# Minna_IO.net
KiCad netlist of a schematic drawn in Altium Designer
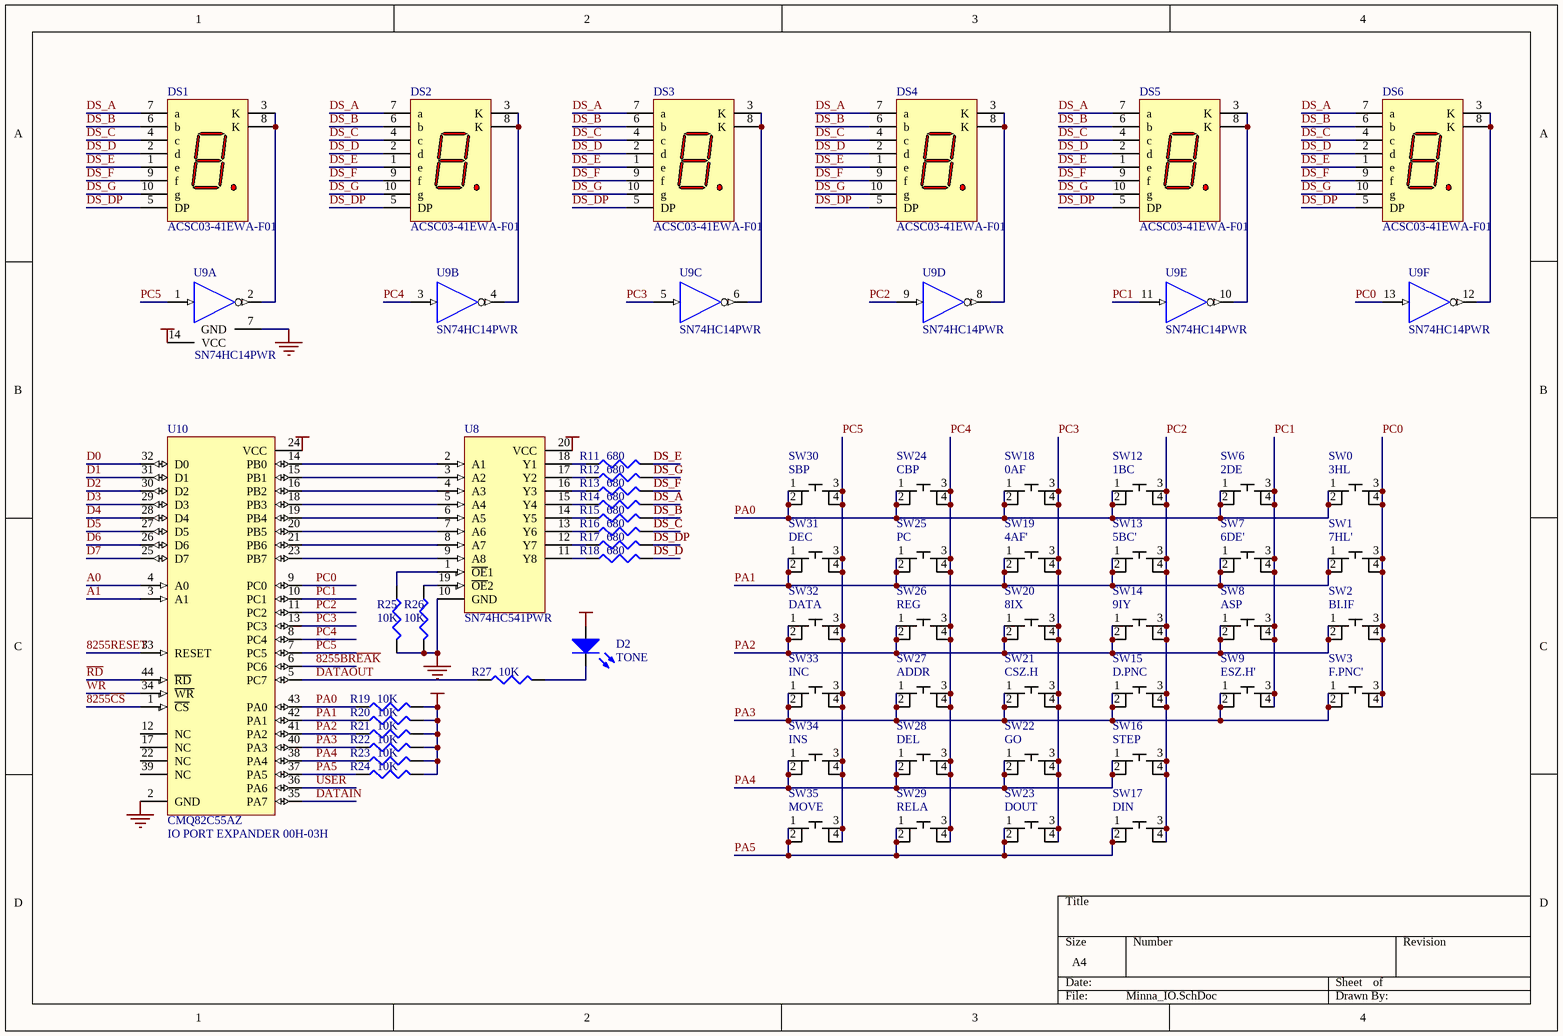
[diagram p0: Minna_IO.SchDoc]

(export (version "E")
  (design (tool "Eeschema 10.0.6"))
  (components
    (comp (ref "D2")
      (value "TONE")
      (footprint "Minna Project:APG1608")
      (description "LED 1.6X0.8MM 571NM GRN CLR SMD")
      (libsource (lib "Minna Project") (part "APG1608CGKC/T"))
    )
    (comp (ref "DS1")
      (value "ACSC03-41EWA-F01")
      (footprint "Minna Project:ACSC03-41EWA-F01")
      (description "DISPLAY 0.3\" 627NM SGL RED SMD")
      (libsource (lib "Minna Project") (part "ACSC03-41EWA-F01"))
    )
    (comp (ref "DS2")
      (value "ACSC03-41EWA-F01")
      (footprint "Minna Project:ACSC03-41EWA-F01")
      (description "DISPLAY 0.3\" 627NM SGL RED SMD")
      (libsource (lib "Minna Project") (part "ACSC03-41EWA-F01"))
    )
    (comp (ref "DS3")
      (value "ACSC03-41EWA-F01")
      (footprint "Minna Project:ACSC03-41EWA-F01")
      (description "DISPLAY 0.3\" 627NM SGL RED SMD")
      (libsource (lib "Minna Project") (part "ACSC03-41EWA-F01"))
    )
    (comp (ref "DS4")
      (value "ACSC03-41EWA-F01")
      (footprint "Minna Project:ACSC03-41EWA-F01")
      (description "DISPLAY 0.3\" 627NM SGL RED SMD")
      (libsource (lib "Minna Project") (part "ACSC03-41EWA-F01"))
    )
    (comp (ref "DS5")
      (value "ACSC03-41EWA-F01")
      (footprint "Minna Project:ACSC03-41EWA-F01")
      (description "DISPLAY 0.3\" 627NM SGL RED SMD")
      (libsource (lib "Minna Project") (part "ACSC03-41EWA-F01"))
    )
    (comp (ref "DS6")
      (value "ACSC03-41EWA-F01")
      (footprint "Minna Project:ACSC03-41EWA-F01")
      (description "DISPLAY 0.3\" 627NM SGL RED SMD")
      (libsource (lib "Minna Project") (part "ACSC03-41EWA-F01"))
    )
    (comp (ref "R11")
      (value "680")
      (footprint "Minna Project:0603")
      (description "RES 680 OHM 1/10W 1% 0603 SMD")
      (libsource (lib "Minna Project") (part "MCR03EZPFX"))
    )
    (comp (ref "R12")
      (value "680")
      (footprint "Minna Project:0603")
      (description "RES 680 OHM 1/10W 1% 0603 SMD")
      (libsource (lib "Minna Project") (part "MCR03EZPFX"))
    )
    (comp (ref "R13")
      (value "680")
      (footprint "Minna Project:0603")
      (description "RES 680 OHM 1/10W 1% 0603 SMD")
      (libsource (lib "Minna Project") (part "MCR03EZPFX"))
    )
    (comp (ref "R14")
      (value "680")
      (footprint "Minna Project:0603")
      (description "RES 680 OHM 1/10W 1% 0603 SMD")
      (libsource (lib "Minna Project") (part "MCR03EZPFX"))
    )
    (comp (ref "R15")
      (value "680")
      (footprint "Minna Project:0603")
      (description "RES 680 OHM 1/10W 1% 0603 SMD")
      (libsource (lib "Minna Project") (part "MCR03EZPFX"))
    )
    (comp (ref "R16")
      (value "680")
      (footprint "Minna Project:0603")
      (description "RES 680 OHM 1/10W 1% 0603 SMD")
      (libsource (lib "Minna Project") (part "MCR03EZPFX"))
    )
    (comp (ref "R17")
      (value "680")
      (footprint "Minna Project:0603")
      (description "RES 680 OHM 1/10W 1% 0603 SMD")
      (libsource (lib "Minna Project") (part "MCR03EZPFX"))
    )
    (comp (ref "R18")
      (value "680")
      (footprint "Minna Project:0603")
      (description "RES 680 OHM 1/10W 1% 0603 SMD")
      (libsource (lib "Minna Project") (part "MCR03EZPFX"))
    )
    (comp (ref "R19")
      (value "10K")
      (footprint "Minna Project:0603")
      (description "RES 10.0K OHM 1/10W 1% 0603 SMD")
      (libsource (lib "Minna Project") (part "MCR03EZPFX"))
    )
    (comp (ref "R20")
      (value "10K")
      (footprint "Minna Project:0603")
      (description "RES 10.0K OHM 1/10W 1% 0603 SMD")
      (libsource (lib "Minna Project") (part "MCR03EZPFX"))
    )
    (comp (ref "R21")
      (value "10K")
      (footprint "Minna Project:0603")
      (description "RES 10.0K OHM 1/10W 1% 0603 SMD")
      (libsource (lib "Minna Project") (part "MCR03EZPFX"))
    )
    (comp (ref "R22")
      (value "10K")
      (footprint "Minna Project:0603")
      (description "RES 10.0K OHM 1/10W 1% 0603 SMD")
      (libsource (lib "Minna Project") (part "MCR03EZPFX"))
    )
    (comp (ref "R23")
      (value "10K")
      (footprint "Minna Project:0603")
      (description "RES 10.0K OHM 1/10W 1% 0603 SMD")
      (libsource (lib "Minna Project") (part "MCR03EZPFX"))
    )
    (comp (ref "R24")
      (value "10K")
      (footprint "Minna Project:0603")
      (description "RES 10.0K OHM 1/10W 1% 0603 SMD")
      (libsource (lib "Minna Project") (part "MCR03EZPFX"))
    )
    (comp (ref "R25")
      (value "10K")
      (footprint "Minna Project:0603")
      (description "RES 10.0K OHM 1/10W 1% 0603 SMD")
      (libsource (lib "Minna Project") (part "MCR03EZPFX"))
    )
    (comp (ref "R26")
      (value "10K")
      (footprint "Minna Project:0603")
      (description "RES 10.0K OHM 1/10W 1% 0603 SMD")
      (libsource (lib "Minna Project") (part "MCR03EZPFX"))
    )
    (comp (ref "R27")
      (value "10K")
      (footprint "Minna Project:0603")
      (description "RES 10.0K OHM 1/10W 1% 0603 SMD")
      (libsource (lib "Minna Project") (part "MCR03EZPFX"))
    )
    (comp (ref "SW0")
      (value "3HL")
      (footprint "Minna Project:PTS645SM43SMTR LFS")
      (description "SWITCH TACT 6MM 160GF H=4.3MM")
      (libsource (lib "Minna Project") (part "PTS645SM43SMTR LFS"))
    )
    (comp (ref "SW1")
      (value "7HL'")
      (footprint "Minna Project:PTS645SM43SMTR LFS")
      (description "SWITCH TACT 6MM 160GF H=4.3MM")
      (libsource (lib "Minna Project") (part "PTS645SM43SMTR LFS"))
    )
    (comp (ref "SW2")
      (value "BI.IF")
      (footprint "Minna Project:PTS645SM43SMTR LFS")
      (description "SWITCH TACT 6MM 160GF H=4.3MM")
      (libsource (lib "Minna Project") (part "PTS645SM43SMTR LFS"))
    )
    (comp (ref "SW3")
      (value "F.PNC'")
      (footprint "Minna Project:PTS645SM43SMTR LFS")
      (description "SWITCH TACT 6MM 160GF H=4.3MM")
      (libsource (lib "Minna Project") (part "PTS645SM43SMTR LFS"))
    )
    (comp (ref "SW6")
      (value "2DE")
      (footprint "Minna Project:PTS645SM43SMTR LFS")
      (description "SWITCH TACT 6MM 160GF H=4.3MM")
      (libsource (lib "Minna Project") (part "PTS645SM43SMTR LFS"))
    )
    (comp (ref "SW7")
      (value "6DE'")
      (footprint "Minna Project:PTS645SM43SMTR LFS")
      (description "SWITCH TACT 6MM 160GF H=4.3MM")
      (libsource (lib "Minna Project") (part "PTS645SM43SMTR LFS"))
    )
    (comp (ref "SW8")
      (value "ASP")
      (footprint "Minna Project:PTS645SM43SMTR LFS")
      (description "SWITCH TACT 6MM 160GF H=4.3MM")
      (libsource (lib "Minna Project") (part "PTS645SM43SMTR LFS"))
    )
    (comp (ref "SW9")
      (value "ESZ.H'")
      (footprint "Minna Project:PTS645SM43SMTR LFS")
      (description "SWITCH TACT 6MM 160GF H=4.3MM")
      (libsource (lib "Minna Project") (part "PTS645SM43SMTR LFS"))
    )
    (comp (ref "SW12")
      (value "1BC")
      (footprint "Minna Project:PTS645SM43SMTR LFS")
      (description "SWITCH TACT 6MM 160GF H=4.3MM")
      (libsource (lib "Minna Project") (part "PTS645SM43SMTR LFS"))
    )
    (comp (ref "SW13")
      (value "5BC'")
      (footprint "Minna Project:PTS645SM43SMTR LFS")
      (description "SWITCH TACT 6MM 160GF H=4.3MM")
      (libsource (lib "Minna Project") (part "PTS645SM43SMTR LFS"))
    )
    (comp (ref "SW14")
      (value "9IY")
      (footprint "Minna Project:PTS645SM43SMTR LFS")
      (description "SWITCH TACT 6MM 160GF H=4.3MM")
      (libsource (lib "Minna Project") (part "PTS645SM43SMTR LFS"))
    )
    (comp (ref "SW15")
      (value "D.PNC")
      (footprint "Minna Project:PTS645SM43SMTR LFS")
      (description "SWITCH TACT 6MM 160GF H=4.3MM")
      (libsource (lib "Minna Project") (part "PTS645SM43SMTR LFS"))
    )
    (comp (ref "SW16")
      (value "STEP")
      (footprint "Minna Project:PTS645SM43SMTR LFS")
      (description "SWITCH TACT 6MM 160GF H=4.3MM")
      (libsource (lib "Minna Project") (part "PTS645SM43SMTR LFS"))
    )
    (comp (ref "SW17")
      (value "DIN")
      (footprint "Minna Project:PTS645SM43SMTR LFS")
      (description "SWITCH TACT 6MM 160GF H=4.3MM")
      (libsource (lib "Minna Project") (part "PTS645SM43SMTR LFS"))
    )
    (comp (ref "SW18")
      (value "0AF")
      (footprint "Minna Project:PTS645SM43SMTR LFS")
      (description "SWITCH TACT 6MM 160GF H=4.3MM")
      (libsource (lib "Minna Project") (part "PTS645SM43SMTR LFS"))
    )
    (comp (ref "SW19")
      (value "4AF'")
      (footprint "Minna Project:PTS645SM43SMTR LFS")
      (description "SWITCH TACT 6MM 160GF H=4.3MM")
      (libsource (lib "Minna Project") (part "PTS645SM43SMTR LFS"))
    )
    (comp (ref "SW20")
      (value "8IX")
      (footprint "Minna Project:PTS645SM43SMTR LFS")
      (description "SWITCH TACT 6MM 160GF H=4.3MM")
      (libsource (lib "Minna Project") (part "PTS645SM43SMTR LFS"))
    )
    (comp (ref "SW21")
      (value "CSZ.H")
      (footprint "Minna Project:PTS645SM43SMTR LFS")
      (description "SWITCH TACT 6MM 160GF H=4.3MM")
      (libsource (lib "Minna Project") (part "PTS645SM43SMTR LFS"))
    )
    (comp (ref "SW22")
      (value "GO")
      (footprint "Minna Project:PTS645SM43SMTR LFS")
      (description "SWITCH TACT 6MM 160GF H=4.3MM")
      (libsource (lib "Minna Project") (part "PTS645SM43SMTR LFS"))
    )
    (comp (ref "SW23")
      (value "DOUT")
      (footprint "Minna Project:PTS645SM43SMTR LFS")
      (description "SWITCH TACT 6MM 160GF H=4.3MM")
      (libsource (lib "Minna Project") (part "PTS645SM43SMTR LFS"))
    )
    (comp (ref "SW24")
      (value "CBP")
      (footprint "Minna Project:PTS645SM43SMTR LFS")
      (description "SWITCH TACT 6MM 160GF H=4.3MM")
      (libsource (lib "Minna Project") (part "PTS645SM43SMTR LFS"))
    )
    (comp (ref "SW25")
      (value "PC")
      (footprint "Minna Project:PTS645SM43SMTR LFS")
      (description "SWITCH TACT 6MM 160GF H=4.3MM")
      (libsource (lib "Minna Project") (part "PTS645SM43SMTR LFS"))
    )
    (comp (ref "SW26")
      (value "REG")
      (footprint "Minna Project:PTS645SM43SMTR LFS")
      (description "SWITCH TACT 6MM 160GF H=4.3MM")
      (libsource (lib "Minna Project") (part "PTS645SM43SMTR LFS"))
    )
    (comp (ref "SW27")
      (value "ADDR")
      (footprint "Minna Project:PTS645SM43SMTR LFS")
      (description "SWITCH TACT 6MM 160GF H=4.3MM")
      (libsource (lib "Minna Project") (part "PTS645SM43SMTR LFS"))
    )
    (comp (ref "SW28")
      (value "DEL")
      (footprint "Minna Project:PTS645SM43SMTR LFS")
      (description "SWITCH TACT 6MM 160GF H=4.3MM")
      (libsource (lib "Minna Project") (part "PTS645SM43SMTR LFS"))
    )
    (comp (ref "SW29")
      (value "RELA")
      (footprint "Minna Project:PTS645SM43SMTR LFS")
      (description "SWITCH TACT 6MM 160GF H=4.3MM")
      (libsource (lib "Minna Project") (part "PTS645SM43SMTR LFS"))
    )
    (comp (ref "SW30")
      (value "SBP")
      (footprint "Minna Project:PTS645SM43SMTR LFS")
      (description "SWITCH TACT 6MM 160GF H=4.3MM")
      (libsource (lib "Minna Project") (part "PTS645SM43SMTR LFS"))
    )
    (comp (ref "SW31")
      (value "DEC")
      (footprint "Minna Project:PTS645SM43SMTR LFS")
      (description "SWITCH TACT 6MM 160GF H=4.3MM")
      (libsource (lib "Minna Project") (part "PTS645SM43SMTR LFS"))
    )
    (comp (ref "SW32")
      (value "DATA")
      (footprint "Minna Project:PTS645SM43SMTR LFS")
      (description "SWITCH TACT 6MM 160GF H=4.3MM")
      (libsource (lib "Minna Project") (part "PTS645SM43SMTR LFS"))
    )
    (comp (ref "SW33")
      (value "INC")
      (footprint "Minna Project:PTS645SM43SMTR LFS")
      (description "SWITCH TACT 6MM 160GF H=4.3MM")
      (libsource (lib "Minna Project") (part "PTS645SM43SMTR LFS"))
    )
    (comp (ref "SW34")
      (value "INS")
      (footprint "Minna Project:PTS645SM43SMTR LFS")
      (description "SWITCH TACT 6MM 160GF H=4.3MM")
      (libsource (lib "Minna Project") (part "PTS645SM43SMTR LFS"))
    )
    (comp (ref "SW35")
      (value "MOVE")
      (footprint "Minna Project:PTS645SM43SMTR LFS")
      (description "SWITCH TACT 6MM 160GF H=4.3MM")
      (libsource (lib "Minna Project") (part "PTS645SM43SMTR LFS"))
    )
    (comp (ref "U8")
      (value "SN74HC541PWR")
      (footprint "Minna Project:PW020")
      (description "IC BUFF/DVR TRI-ST 8BIT 20TSSOP")
      (libsource (lib "Minna Project") (part "SN74HC541PWR"))
    )
    (comp (ref "U9")
      (value "SN74HC14PWR")
      (footprint "Minna Project:PW014")
      (description "IC HEX SCHMITT-TRIG INV 14-TSSOP")
      (libsource (lib "Minna Project") (part "SN74HC14PWR"))
    )
    (comp (ref "U10")
      (value "CMQ82C55AZ")
      (footprint "Minna Project:MQFP-44")
      (description "IC I/O EXPANDER 24B 44MQFP")
      (fields (field (name "NOTES") "IO PORT EXPANDER 00H-03H"))
      (libsource (lib "Minna Project") (part "CMQ82C55AZ"))
    )
  )
  (nets
    (net (code "1") (name "/8255RESET") (class "Default")
      (node (ref "U10") (pin "33") (pinfunction "RESET_33") (pintype "input"))
    )
    (net (code "2") (name "/8255~{BREAK}") (class "Default")
      (node (ref "U10") (pin "6") (pinfunction "PC6_6") (pintype "bidirectional"))
    )
    (net (code "3") (name "/8255~{CS}") (class "Default")
      (node (ref "U10") (pin "1") (pinfunction "~{CS}_1") (pintype "input"))
    )
    (net (code "4") (name "/A0") (class "Default")
      (node (ref "U10") (pin "4") (pinfunction "A0_4") (pintype "input"))
    )
    (net (code "5") (name "/A1") (class "Default")
      (node (ref "U10") (pin "3") (pinfunction "A1_3") (pintype "input"))
    )
    (net (code "6") (name "/D0") (class "Default")
      (node (ref "U10") (pin "32") (pinfunction "D0_32") (pintype "bidirectional"))
    )
    (net (code "7") (name "/D1") (class "Default")
      (node (ref "U10") (pin "31") (pinfunction "D1_31") (pintype "bidirectional"))
    )
    (net (code "8") (name "/D2") (class "Default")
      (node (ref "U10") (pin "30") (pinfunction "D2_30") (pintype "bidirectional"))
    )
    (net (code "9") (name "/D3") (class "Default")
      (node (ref "U10") (pin "29") (pinfunction "D3_29") (pintype "bidirectional"))
    )
    (net (code "10") (name "/D4") (class "Default")
      (node (ref "U10") (pin "28") (pinfunction "D4_28") (pintype "bidirectional"))
    )
    (net (code "11") (name "/D5") (class "Default")
      (node (ref "U10") (pin "27") (pinfunction "D5_27") (pintype "bidirectional"))
    )
    (net (code "12") (name "/D6") (class "Default")
      (node (ref "U10") (pin "26") (pinfunction "D6_26") (pintype "bidirectional"))
    )
    (net (code "13") (name "/D7") (class "Default")
      (node (ref "U10") (pin "25") (pinfunction "D7_25") (pintype "bidirectional"))
    )
    (net (code "14") (name "/DATAIN") (class "Default")
      (node (ref "U10") (pin "35") (pinfunction "PA7_35") (pintype "bidirectional"))
    )
    (net (code "15") (name "/DATAOUT") (class "Default")
      (node (ref "R27") (pin "1") (pinfunction "1_1") (pintype "passive"))
      (node (ref "U10") (pin "5") (pinfunction "PC7_5") (pintype "bidirectional"))
    )
    (net (code "16") (name "/DS_A") (class "Default")
      (node (ref "DS1") (pin "7") (pinfunction "a_7") (pintype "passive"))
      (node (ref "DS2") (pin "7") (pinfunction "a_7") (pintype "passive"))
      (node (ref "DS3") (pin "7") (pinfunction "a_7") (pintype "passive"))
      (node (ref "DS4") (pin "7") (pinfunction "a_7") (pintype "passive"))
      (node (ref "DS5") (pin "7") (pinfunction "a_7") (pintype "passive"))
      (node (ref "DS6") (pin "7") (pinfunction "a_7") (pintype "passive"))
      (node (ref "R14") (pin "2") (pinfunction "2_2") (pintype "passive"))
    )
    (net (code "17") (name "/DS_B") (class "Default")
      (node (ref "DS1") (pin "6") (pinfunction "b_6") (pintype "passive"))
      (node (ref "DS2") (pin "6") (pinfunction "b_6") (pintype "passive"))
      (node (ref "DS3") (pin "6") (pinfunction "b_6") (pintype "passive"))
      (node (ref "DS4") (pin "6") (pinfunction "b_6") (pintype "passive"))
      (node (ref "DS5") (pin "6") (pinfunction "b_6") (pintype "passive"))
      (node (ref "DS6") (pin "6") (pinfunction "b_6") (pintype "passive"))
      (node (ref "R15") (pin "2") (pinfunction "2_2") (pintype "passive"))
    )
    (net (code "18") (name "/DS_C") (class "Default")
      (node (ref "DS1") (pin "4") (pinfunction "c_4") (pintype "passive"))
      (node (ref "DS2") (pin "4") (pinfunction "c_4") (pintype "passive"))
      (node (ref "DS3") (pin "4") (pinfunction "c_4") (pintype "passive"))
      (node (ref "DS4") (pin "4") (pinfunction "c_4") (pintype "passive"))
      (node (ref "DS5") (pin "4") (pinfunction "c_4") (pintype "passive"))
      (node (ref "DS6") (pin "4") (pinfunction "c_4") (pintype "passive"))
      (node (ref "R16") (pin "2") (pinfunction "2_2") (pintype "passive"))
    )
    (net (code "19") (name "/DS_D") (class "Default")
      (node (ref "DS1") (pin "2") (pinfunction "d_2") (pintype "passive"))
      (node (ref "DS2") (pin "2") (pinfunction "d_2") (pintype "passive"))
      (node (ref "DS3") (pin "2") (pinfunction "d_2") (pintype "passive"))
      (node (ref "DS4") (pin "2") (pinfunction "d_2") (pintype "passive"))
      (node (ref "DS5") (pin "2") (pinfunction "d_2") (pintype "passive"))
      (node (ref "DS6") (pin "2") (pinfunction "d_2") (pintype "passive"))
      (node (ref "R18") (pin "2") (pinfunction "2_2") (pintype "passive"))
    )
    (net (code "20") (name "/DS_DP") (class "Default")
      (node (ref "DS1") (pin "5") (pinfunction "DP_5") (pintype "passive"))
      (node (ref "DS2") (pin "5") (pinfunction "DP_5") (pintype "passive"))
      (node (ref "DS3") (pin "5") (pinfunction "DP_5") (pintype "passive"))
      (node (ref "DS4") (pin "5") (pinfunction "DP_5") (pintype "passive"))
      (node (ref "DS5") (pin "5") (pinfunction "DP_5") (pintype "passive"))
      (node (ref "DS6") (pin "5") (pinfunction "DP_5") (pintype "passive"))
      (node (ref "R17") (pin "2") (pinfunction "2_2") (pintype "passive"))
    )
    (net (code "21") (name "/DS_E") (class "Default")
      (node (ref "DS1") (pin "1") (pinfunction "e_1") (pintype "passive"))
      (node (ref "DS2") (pin "1") (pinfunction "e_1") (pintype "passive"))
      (node (ref "DS3") (pin "1") (pinfunction "e_1") (pintype "passive"))
      (node (ref "DS4") (pin "1") (pinfunction "e_1") (pintype "passive"))
      (node (ref "DS5") (pin "1") (pinfunction "e_1") (pintype "passive"))
      (node (ref "DS6") (pin "1") (pinfunction "e_1") (pintype "passive"))
      (node (ref "R11") (pin "2") (pinfunction "2_2") (pintype "passive"))
    )
    (net (code "22") (name "/DS_F") (class "Default")
      (node (ref "DS1") (pin "9") (pinfunction "f_9") (pintype "passive"))
      (node (ref "DS2") (pin "9") (pinfunction "f_9") (pintype "passive"))
      (node (ref "DS3") (pin "9") (pinfunction "f_9") (pintype "passive"))
      (node (ref "DS4") (pin "9") (pinfunction "f_9") (pintype "passive"))
      (node (ref "DS5") (pin "9") (pinfunction "f_9") (pintype "passive"))
      (node (ref "DS6") (pin "9") (pinfunction "f_9") (pintype "passive"))
      (node (ref "R13") (pin "2") (pinfunction "2_2") (pintype "passive"))
    )
    (net (code "23") (name "/DS_G") (class "Default")
      (node (ref "DS1") (pin "10") (pinfunction "g_10") (pintype "passive"))
      (node (ref "DS2") (pin "10") (pinfunction "g_10") (pintype "passive"))
      (node (ref "DS3") (pin "10") (pinfunction "g_10") (pintype "passive"))
      (node (ref "DS4") (pin "10") (pinfunction "g_10") (pintype "passive"))
      (node (ref "DS5") (pin "10") (pinfunction "g_10") (pintype "passive"))
      (node (ref "DS6") (pin "10") (pinfunction "g_10") (pintype "passive"))
      (node (ref "R12") (pin "2") (pinfunction "2_2") (pintype "passive"))
    )
    (net (code "24") (name "/PA0") (class "Default")
      (node (ref "R19") (pin "1") (pinfunction "1_1") (pintype "passive"))
      (node (ref "SW0") (pin "1") (pinfunction "1_1") (pintype "passive"))
      (node (ref "SW0") (pin "2") (pinfunction "2_2") (pintype "passive"))
      (node (ref "SW12") (pin "1") (pinfunction "1_1") (pintype "passive"))
      (node (ref "SW12") (pin "2") (pinfunction "2_2") (pintype "passive"))
      (node (ref "SW18") (pin "1") (pinfunction "1_1") (pintype "passive"))
      (node (ref "SW18") (pin "2") (pinfunction "2_2") (pintype "passive"))
      (node (ref "SW24") (pin "1") (pinfunction "1_1") (pintype "passive"))
      (node (ref "SW24") (pin "2") (pinfunction "2_2") (pintype "passive"))
      (node (ref "SW30") (pin "1") (pinfunction "1_1") (pintype "passive"))
      (node (ref "SW30") (pin "2") (pinfunction "2_2") (pintype "passive"))
      (node (ref "SW6") (pin "1") (pinfunction "1_1") (pintype "passive"))
      (node (ref "SW6") (pin "2") (pinfunction "2_2") (pintype "passive"))
      (node (ref "U10") (pin "43") (pinfunction "PA0_43") (pintype "bidirectional"))
    )
    (net (code "25") (name "/PA1") (class "Default")
      (node (ref "R20") (pin "1") (pinfunction "1_1") (pintype "passive"))
      (node (ref "SW1") (pin "1") (pinfunction "1_1") (pintype "passive"))
      (node (ref "SW1") (pin "2") (pinfunction "2_2") (pintype "passive"))
      (node (ref "SW13") (pin "1") (pinfunction "1_1") (pintype "passive"))
      (node (ref "SW13") (pin "2") (pinfunction "2_2") (pintype "passive"))
      (node (ref "SW19") (pin "1") (pinfunction "1_1") (pintype "passive"))
      (node (ref "SW19") (pin "2") (pinfunction "2_2") (pintype "passive"))
      (node (ref "SW25") (pin "1") (pinfunction "1_1") (pintype "passive"))
      (node (ref "SW25") (pin "2") (pinfunction "2_2") (pintype "passive"))
      (node (ref "SW31") (pin "1") (pinfunction "1_1") (pintype "passive"))
      (node (ref "SW31") (pin "2") (pinfunction "2_2") (pintype "passive"))
      (node (ref "SW7") (pin "1") (pinfunction "1_1") (pintype "passive"))
      (node (ref "SW7") (pin "2") (pinfunction "2_2") (pintype "passive"))
      (node (ref "U10") (pin "42") (pinfunction "PA1_42") (pintype "bidirectional"))
    )
    (net (code "26") (name "/PA2") (class "Default")
      (node (ref "R21") (pin "1") (pinfunction "1_1") (pintype "passive"))
      (node (ref "SW14") (pin "1") (pinfunction "1_1") (pintype "passive"))
      (node (ref "SW14") (pin "2") (pinfunction "2_2") (pintype "passive"))
      (node (ref "SW2") (pin "1") (pinfunction "1_1") (pintype "passive"))
      (node (ref "SW2") (pin "2") (pinfunction "2_2") (pintype "passive"))
      (node (ref "SW20") (pin "1") (pinfunction "1_1") (pintype "passive"))
      (node (ref "SW20") (pin "2") (pinfunction "2_2") (pintype "passive"))
      (node (ref "SW26") (pin "1") (pinfunction "1_1") (pintype "passive"))
      (node (ref "SW26") (pin "2") (pinfunction "2_2") (pintype "passive"))
      (node (ref "SW32") (pin "1") (pinfunction "1_1") (pintype "passive"))
      (node (ref "SW32") (pin "2") (pinfunction "2_2") (pintype "passive"))
      (node (ref "SW8") (pin "1") (pinfunction "1_1") (pintype "passive"))
      (node (ref "SW8") (pin "2") (pinfunction "2_2") (pintype "passive"))
      (node (ref "U10") (pin "41") (pinfunction "PA2_41") (pintype "bidirectional"))
    )
    (net (code "27") (name "/PA3") (class "Default")
      (node (ref "R22") (pin "1") (pinfunction "1_1") (pintype "passive"))
      (node (ref "SW15") (pin "1") (pinfunction "1_1") (pintype "passive"))
      (node (ref "SW15") (pin "2") (pinfunction "2_2") (pintype "passive"))
      (node (ref "SW21") (pin "1") (pinfunction "1_1") (pintype "passive"))
      (node (ref "SW21") (pin "2") (pinfunction "2_2") (pintype "passive"))
      (node (ref "SW27") (pin "1") (pinfunction "1_1") (pintype "passive"))
      (node (ref "SW27") (pin "2") (pinfunction "2_2") (pintype "passive"))
      (node (ref "SW3") (pin "1") (pinfunction "1_1") (pintype "passive"))
      (node (ref "SW3") (pin "2") (pinfunction "2_2") (pintype "passive"))
      (node (ref "SW33") (pin "1") (pinfunction "1_1") (pintype "passive"))
      (node (ref "SW33") (pin "2") (pinfunction "2_2") (pintype "passive"))
      (node (ref "SW9") (pin "1") (pinfunction "1_1") (pintype "passive"))
      (node (ref "SW9") (pin "2") (pinfunction "2_2") (pintype "passive"))
      (node (ref "U10") (pin "40") (pinfunction "PA3_40") (pintype "bidirectional"))
    )
    (net (code "28") (name "/PA4") (class "Default")
      (node (ref "R23") (pin "1") (pinfunction "1_1") (pintype "passive"))
      (node (ref "SW16") (pin "1") (pinfunction "1_1") (pintype "passive"))
      (node (ref "SW16") (pin "2") (pinfunction "2_2") (pintype "passive"))
      (node (ref "SW22") (pin "1") (pinfunction "1_1") (pintype "passive"))
      (node (ref "SW22") (pin "2") (pinfunction "2_2") (pintype "passive"))
      (node (ref "SW28") (pin "1") (pinfunction "1_1") (pintype "passive"))
      (node (ref "SW28") (pin "2") (pinfunction "2_2") (pintype "passive"))
      (node (ref "SW34") (pin "1") (pinfunction "1_1") (pintype "passive"))
      (node (ref "SW34") (pin "2") (pinfunction "2_2") (pintype "passive"))
      (node (ref "U10") (pin "38") (pinfunction "PA4_38") (pintype "bidirectional"))
    )
    (net (code "29") (name "/PA5") (class "Default")
      (node (ref "R24") (pin "1") (pinfunction "1_1") (pintype "passive"))
      (node (ref "SW17") (pin "1") (pinfunction "1_1") (pintype "passive"))
      (node (ref "SW17") (pin "2") (pinfunction "2_2") (pintype "passive"))
      (node (ref "SW23") (pin "1") (pinfunction "1_1") (pintype "passive"))
      (node (ref "SW23") (pin "2") (pinfunction "2_2") (pintype "passive"))
      (node (ref "SW29") (pin "1") (pinfunction "1_1") (pintype "passive"))
      (node (ref "SW29") (pin "2") (pinfunction "2_2") (pintype "passive"))
      (node (ref "SW35") (pin "1") (pinfunction "1_1") (pintype "passive"))
      (node (ref "SW35") (pin "2") (pinfunction "2_2") (pintype "passive"))
      (node (ref "U10") (pin "37") (pinfunction "PA5_37") (pintype "bidirectional"))
    )
    (net (code "30") (name "/PC0") (class "Default")
      (node (ref "SW0") (pin "3") (pinfunction "3_3") (pintype "passive"))
      (node (ref "SW0") (pin "4") (pinfunction "4_4") (pintype "passive"))
      (node (ref "SW1") (pin "3") (pinfunction "3_3") (pintype "passive"))
      (node (ref "SW1") (pin "4") (pinfunction "4_4") (pintype "passive"))
      (node (ref "SW2") (pin "3") (pinfunction "3_3") (pintype "passive"))
      (node (ref "SW2") (pin "4") (pinfunction "4_4") (pintype "passive"))
      (node (ref "SW3") (pin "3") (pinfunction "3_3") (pintype "passive"))
      (node (ref "SW3") (pin "4") (pinfunction "4_4") (pintype "passive"))
      (node (ref "U10") (pin "9") (pinfunction "PC0_9") (pintype "bidirectional"))
      (node (ref "U9") (pin "13") (pinfunction "A_13") (pintype "input"))
    )
    (net (code "31") (name "/PC1") (class "Default")
      (node (ref "SW6") (pin "3") (pinfunction "3_3") (pintype "passive"))
      (node (ref "SW6") (pin "4") (pinfunction "4_4") (pintype "passive"))
      (node (ref "SW7") (pin "3") (pinfunction "3_3") (pintype "passive"))
      (node (ref "SW7") (pin "4") (pinfunction "4_4") (pintype "passive"))
      (node (ref "SW8") (pin "3") (pinfunction "3_3") (pintype "passive"))
      (node (ref "SW8") (pin "4") (pinfunction "4_4") (pintype "passive"))
      (node (ref "SW9") (pin "3") (pinfunction "3_3") (pintype "passive"))
      (node (ref "SW9") (pin "4") (pinfunction "4_4") (pintype "passive"))
      (node (ref "U10") (pin "10") (pinfunction "PC1_10") (pintype "bidirectional"))
      (node (ref "U9") (pin "11") (pinfunction "A_11") (pintype "input"))
    )
    (net (code "32") (name "/PC2") (class "Default")
      (node (ref "SW12") (pin "3") (pinfunction "3_3") (pintype "passive"))
      (node (ref "SW12") (pin "4") (pinfunction "4_4") (pintype "passive"))
      (node (ref "SW13") (pin "3") (pinfunction "3_3") (pintype "passive"))
      (node (ref "SW13") (pin "4") (pinfunction "4_4") (pintype "passive"))
      (node (ref "SW14") (pin "3") (pinfunction "3_3") (pintype "passive"))
      (node (ref "SW14") (pin "4") (pinfunction "4_4") (pintype "passive"))
      (node (ref "SW15") (pin "3") (pinfunction "3_3") (pintype "passive"))
      (node (ref "SW15") (pin "4") (pinfunction "4_4") (pintype "passive"))
      (node (ref "SW16") (pin "3") (pinfunction "3_3") (pintype "passive"))
      (node (ref "SW16") (pin "4") (pinfunction "4_4") (pintype "passive"))
      (node (ref "SW17") (pin "3") (pinfunction "3_3") (pintype "passive"))
      (node (ref "SW17") (pin "4") (pinfunction "4_4") (pintype "passive"))
      (node (ref "U10") (pin "11") (pinfunction "PC2_11") (pintype "bidirectional"))
      (node (ref "U9") (pin "9") (pinfunction "A_9") (pintype "input"))
    )
    (net (code "33") (name "/PC3") (class "Default")
      (node (ref "SW18") (pin "3") (pinfunction "3_3") (pintype "passive"))
      (node (ref "SW18") (pin "4") (pinfunction "4_4") (pintype "passive"))
      (node (ref "SW19") (pin "3") (pinfunction "3_3") (pintype "passive"))
      (node (ref "SW19") (pin "4") (pinfunction "4_4") (pintype "passive"))
      (node (ref "SW20") (pin "3") (pinfunction "3_3") (pintype "passive"))
      (node (ref "SW20") (pin "4") (pinfunction "4_4") (pintype "passive"))
      (node (ref "SW21") (pin "3") (pinfunction "3_3") (pintype "passive"))
      (node (ref "SW21") (pin "4") (pinfunction "4_4") (pintype "passive"))
      (node (ref "SW22") (pin "3") (pinfunction "3_3") (pintype "passive"))
      (node (ref "SW22") (pin "4") (pinfunction "4_4") (pintype "passive"))
      (node (ref "SW23") (pin "3") (pinfunction "3_3") (pintype "passive"))
      (node (ref "SW23") (pin "4") (pinfunction "4_4") (pintype "passive"))
      (node (ref "U10") (pin "13") (pinfunction "PC3_13") (pintype "bidirectional"))
      (node (ref "U9") (pin "5") (pinfunction "A_5") (pintype "input"))
    )
    (net (code "34") (name "/PC4") (class "Default")
      (node (ref "SW24") (pin "3") (pinfunction "3_3") (pintype "passive"))
      (node (ref "SW24") (pin "4") (pinfunction "4_4") (pintype "passive"))
      (node (ref "SW25") (pin "3") (pinfunction "3_3") (pintype "passive"))
      (node (ref "SW25") (pin "4") (pinfunction "4_4") (pintype "passive"))
      (node (ref "SW26") (pin "3") (pinfunction "3_3") (pintype "passive"))
      (node (ref "SW26") (pin "4") (pinfunction "4_4") (pintype "passive"))
      (node (ref "SW27") (pin "3") (pinfunction "3_3") (pintype "passive"))
      (node (ref "SW27") (pin "4") (pinfunction "4_4") (pintype "passive"))
      (node (ref "SW28") (pin "3") (pinfunction "3_3") (pintype "passive"))
      (node (ref "SW28") (pin "4") (pinfunction "4_4") (pintype "passive"))
      (node (ref "SW29") (pin "3") (pinfunction "3_3") (pintype "passive"))
      (node (ref "SW29") (pin "4") (pinfunction "4_4") (pintype "passive"))
      (node (ref "U10") (pin "8") (pinfunction "PC4_8") (pintype "bidirectional"))
      (node (ref "U9") (pin "3") (pinfunction "A_3") (pintype "input"))
    )
    (net (code "35") (name "/PC5") (class "Default")
      (node (ref "SW30") (pin "3") (pinfunction "3_3") (pintype "passive"))
      (node (ref "SW30") (pin "4") (pinfunction "4_4") (pintype "passive"))
      (node (ref "SW31") (pin "3") (pinfunction "3_3") (pintype "passive"))
      (node (ref "SW31") (pin "4") (pinfunction "4_4") (pintype "passive"))
      (node (ref "SW32") (pin "3") (pinfunction "3_3") (pintype "passive"))
      (node (ref "SW32") (pin "4") (pinfunction "4_4") (pintype "passive"))
      (node (ref "SW33") (pin "3") (pinfunction "3_3") (pintype "passive"))
      (node (ref "SW33") (pin "4") (pinfunction "4_4") (pintype "passive"))
      (node (ref "SW34") (pin "3") (pinfunction "3_3") (pintype "passive"))
      (node (ref "SW34") (pin "4") (pinfunction "4_4") (pintype "passive"))
      (node (ref "SW35") (pin "3") (pinfunction "3_3") (pintype "passive"))
      (node (ref "SW35") (pin "4") (pinfunction "4_4") (pintype "passive"))
      (node (ref "U10") (pin "7") (pinfunction "PC5_7") (pintype "bidirectional"))
      (node (ref "U9") (pin "1") (pinfunction "A_1") (pintype "input"))
    )
    (net (code "36") (name "/USER") (class "Default")
      (node (ref "U10") (pin "36") (pinfunction "PA6_36") (pintype "bidirectional"))
    )
    (net (code "37") (name "/~{RD}") (class "Default")
      (node (ref "U10") (pin "44") (pinfunction "~{RD}_44") (pintype "input"))
    )
    (net (code "38") (name "/~{WR}") (class "Default")
      (node (ref "U10") (pin "34") (pinfunction "~{WR}_34") (pintype "input"))
    )
    (net (code "39") (name "GND") (class "Default")
      (node (ref "R25") (pin "2") (pinfunction "2_2") (pintype "passive"))
      (node (ref "R26") (pin "2") (pinfunction "2_2") (pintype "passive"))
      (node (ref "U10") (pin "2") (pinfunction "GND_2") (pintype "power_in"))
      (node (ref "U8") (pin "10") (pinfunction "GND_10") (pintype "power_in"))
      (node (ref "U9") (pin "7") (pinfunction "GND_7") (pintype "power_in"))
    )
    (net (code "40") (name "Net-(D2-K)") (class "Default")
      (node (ref "D2") (pin "2") (pinfunction "K_2") (pintype "passive"))
      (node (ref "R27") (pin "2") (pinfunction "2_2") (pintype "passive"))
    )
    (net (code "41") (name "Net-(U8-Y1)") (class "Default")
      (node (ref "R11") (pin "1") (pinfunction "1_1") (pintype "passive"))
      (node (ref "U8") (pin "18") (pinfunction "Y1_18") (pintype "tri_state"))
    )
    (net (code "42") (name "Net-(U8-Y2)") (class "Default")
      (node (ref "R12") (pin "1") (pinfunction "1_1") (pintype "passive"))
      (node (ref "U8") (pin "17") (pinfunction "Y2_17") (pintype "tri_state"))
    )
    (net (code "43") (name "Net-(U8-Y3)") (class "Default")
      (node (ref "R13") (pin "1") (pinfunction "1_1") (pintype "passive"))
      (node (ref "U8") (pin "16") (pinfunction "Y3_16") (pintype "tri_state"))
    )
    (net (code "44") (name "Net-(U8-Y4)") (class "Default")
      (node (ref "R14") (pin "1") (pinfunction "1_1") (pintype "passive"))
      (node (ref "U8") (pin "15") (pinfunction "Y4_15") (pintype "tri_state"))
    )
    (net (code "45") (name "Net-(U8-Y5)") (class "Default")
      (node (ref "R15") (pin "1") (pinfunction "1_1") (pintype "passive"))
      (node (ref "U8") (pin "14") (pinfunction "Y5_14") (pintype "tri_state"))
    )
    (net (code "46") (name "Net-(U8-Y6)") (class "Default")
      (node (ref "R16") (pin "1") (pinfunction "1_1") (pintype "passive"))
      (node (ref "U8") (pin "13") (pinfunction "Y6_13") (pintype "tri_state"))
    )
    (net (code "47") (name "Net-(U8-Y7)") (class "Default")
      (node (ref "R17") (pin "1") (pinfunction "1_1") (pintype "passive"))
      (node (ref "U8") (pin "12") (pinfunction "Y7_12") (pintype "tri_state"))
    )
    (net (code "48") (name "Net-(U8-Y8)") (class "Default")
      (node (ref "R18") (pin "1") (pinfunction "1_1") (pintype "passive"))
      (node (ref "U8") (pin "11") (pinfunction "Y8_11") (pintype "tri_state"))
    )
    (net (code "49") (name "Net-(U8-~{OE}1)") (class "Default")
      (node (ref "R25") (pin "1") (pinfunction "1_1") (pintype "passive"))
      (node (ref "U8") (pin "1") (pinfunction "~{OE}1_1") (pintype "input"))
    )
    (net (code "50") (name "Net-(U8-~{OE}2)") (class "Default")
      (node (ref "R26") (pin "1") (pinfunction "1_1") (pintype "passive"))
      (node (ref "U8") (pin "19") (pinfunction "~{OE}2_19") (pintype "input"))
    )
    (net (code "51") (name "Net-(U9A-Y)") (class "Default")
      (node (ref "DS1") (pin "3") (pinfunction "K_3") (pintype "passive"))
      (node (ref "DS1") (pin "8") (pinfunction "K_8") (pintype "passive"))
      (node (ref "U9") (pin "2") (pinfunction "Y_2") (pintype "output"))
    )
    (net (code "52") (name "Net-(U9B-Y)") (class "Default")
      (node (ref "DS2") (pin "3") (pinfunction "K_3") (pintype "passive"))
      (node (ref "DS2") (pin "8") (pinfunction "K_8") (pintype "passive"))
      (node (ref "U9") (pin "4") (pinfunction "Y_4") (pintype "output"))
    )
    (net (code "53") (name "Net-(U9C-Y)") (class "Default")
      (node (ref "DS3") (pin "3") (pinfunction "K_3") (pintype "passive"))
      (node (ref "DS3") (pin "8") (pinfunction "K_8") (pintype "passive"))
      (node (ref "U9") (pin "6") (pinfunction "Y_6") (pintype "output"))
    )
    (net (code "54") (name "Net-(U9D-Y)") (class "Default")
      (node (ref "DS4") (pin "3") (pinfunction "K_3") (pintype "passive"))
      (node (ref "DS4") (pin "8") (pinfunction "K_8") (pintype "passive"))
      (node (ref "U9") (pin "8") (pinfunction "Y_8") (pintype "output"))
    )
    (net (code "55") (name "Net-(U9E-Y)") (class "Default")
      (node (ref "DS5") (pin "3") (pinfunction "K_3") (pintype "passive"))
      (node (ref "DS5") (pin "8") (pinfunction "K_8") (pintype "passive"))
      (node (ref "U9") (pin "10") (pinfunction "Y_10") (pintype "output"))
    )
    (net (code "56") (name "Net-(U9F-Y)") (class "Default")
      (node (ref "DS6") (pin "3") (pinfunction "K_3") (pintype "passive"))
      (node (ref "DS6") (pin "8") (pinfunction "K_8") (pintype "passive"))
      (node (ref "U9") (pin "12") (pinfunction "Y_12") (pintype "output"))
    )
    (net (code "57") (name "Net-(U10-PB0)") (class "Default")
      (node (ref "U10") (pin "14") (pinfunction "PB0_14") (pintype "bidirectional"))
      (node (ref "U8") (pin "2") (pinfunction "A1_2") (pintype "input"))
    )
    (net (code "58") (name "Net-(U10-PB1)") (class "Default")
      (node (ref "U10") (pin "15") (pinfunction "PB1_15") (pintype "bidirectional"))
      (node (ref "U8") (pin "3") (pinfunction "A2_3") (pintype "input"))
    )
    (net (code "59") (name "Net-(U10-PB2)") (class "Default")
      (node (ref "U10") (pin "16") (pinfunction "PB2_16") (pintype "bidirectional"))
      (node (ref "U8") (pin "4") (pinfunction "A3_4") (pintype "input"))
    )
    (net (code "60") (name "Net-(U10-PB3)") (class "Default")
      (node (ref "U10") (pin "18") (pinfunction "PB3_18") (pintype "bidirectional"))
      (node (ref "U8") (pin "5") (pinfunction "A4_5") (pintype "input"))
    )
    (net (code "61") (name "Net-(U10-PB4)") (class "Default")
      (node (ref "U10") (pin "19") (pinfunction "PB4_19") (pintype "bidirectional"))
      (node (ref "U8") (pin "6") (pinfunction "A5_6") (pintype "input"))
    )
    (net (code "62") (name "Net-(U10-PB5)") (class "Default")
      (node (ref "U10") (pin "20") (pinfunction "PB5_20") (pintype "bidirectional"))
      (node (ref "U8") (pin "7") (pinfunction "A6_7") (pintype "input"))
    )
    (net (code "63") (name "Net-(U10-PB6)") (class "Default")
      (node (ref "U10") (pin "21") (pinfunction "PB6_21") (pintype "bidirectional"))
      (node (ref "U8") (pin "8") (pinfunction "A7_8") (pintype "input"))
    )
    (net (code "64") (name "Net-(U10-PB7)") (class "Default")
      (node (ref "U10") (pin "23") (pinfunction "PB7_23") (pintype "bidirectional"))
      (node (ref "U8") (pin "9") (pinfunction "A8_9") (pintype "input"))
    )
    (net (code "65") (name "VCC") (class "Default")
      (node (ref "D2") (pin "1") (pinfunction "A_1") (pintype "passive"))
      (node (ref "R19") (pin "2") (pinfunction "2_2") (pintype "passive"))
      (node (ref "R20") (pin "2") (pinfunction "2_2") (pintype "passive"))
      (node (ref "R21") (pin "2") (pinfunction "2_2") (pintype "passive"))
      (node (ref "R22") (pin "2") (pinfunction "2_2") (pintype "passive"))
      (node (ref "R23") (pin "2") (pinfunction "2_2") (pintype "passive"))
      (node (ref "R24") (pin "2") (pinfunction "2_2") (pintype "passive"))
      (node (ref "U10") (pin "24") (pinfunction "VCC_24") (pintype "power_in"))
      (node (ref "U8") (pin "20") (pinfunction "VCC_20") (pintype "power_in"))
      (node (ref "U9") (pin "14") (pinfunction "VCC_14") (pintype "power_in"))
    )
    (net (code "66") (name "unconnected-(U10-NC-Pad12)") (class "Default")
      (node (ref "U10") (pin "12") (pinfunction "NC_12") (pintype "passive"))
    )
    (net (code "67") (name "unconnected-(U10-NC-Pad17)") (class "Default")
      (node (ref "U10") (pin "17") (pinfunction "NC_17") (pintype "passive"))
    )
    (net (code "68") (name "unconnected-(U10-NC-Pad22)") (class "Default")
      (node (ref "U10") (pin "22") (pinfunction "NC_22") (pintype "passive"))
    )
    (net (code "69") (name "unconnected-(U10-NC-Pad39)") (class "Default")
      (node (ref "U10") (pin "39") (pinfunction "NC_39") (pintype "passive"))
    )
  )
)
